# MineralFire_v1.net
KiCad netlist of a schematic drawn in EAGLE
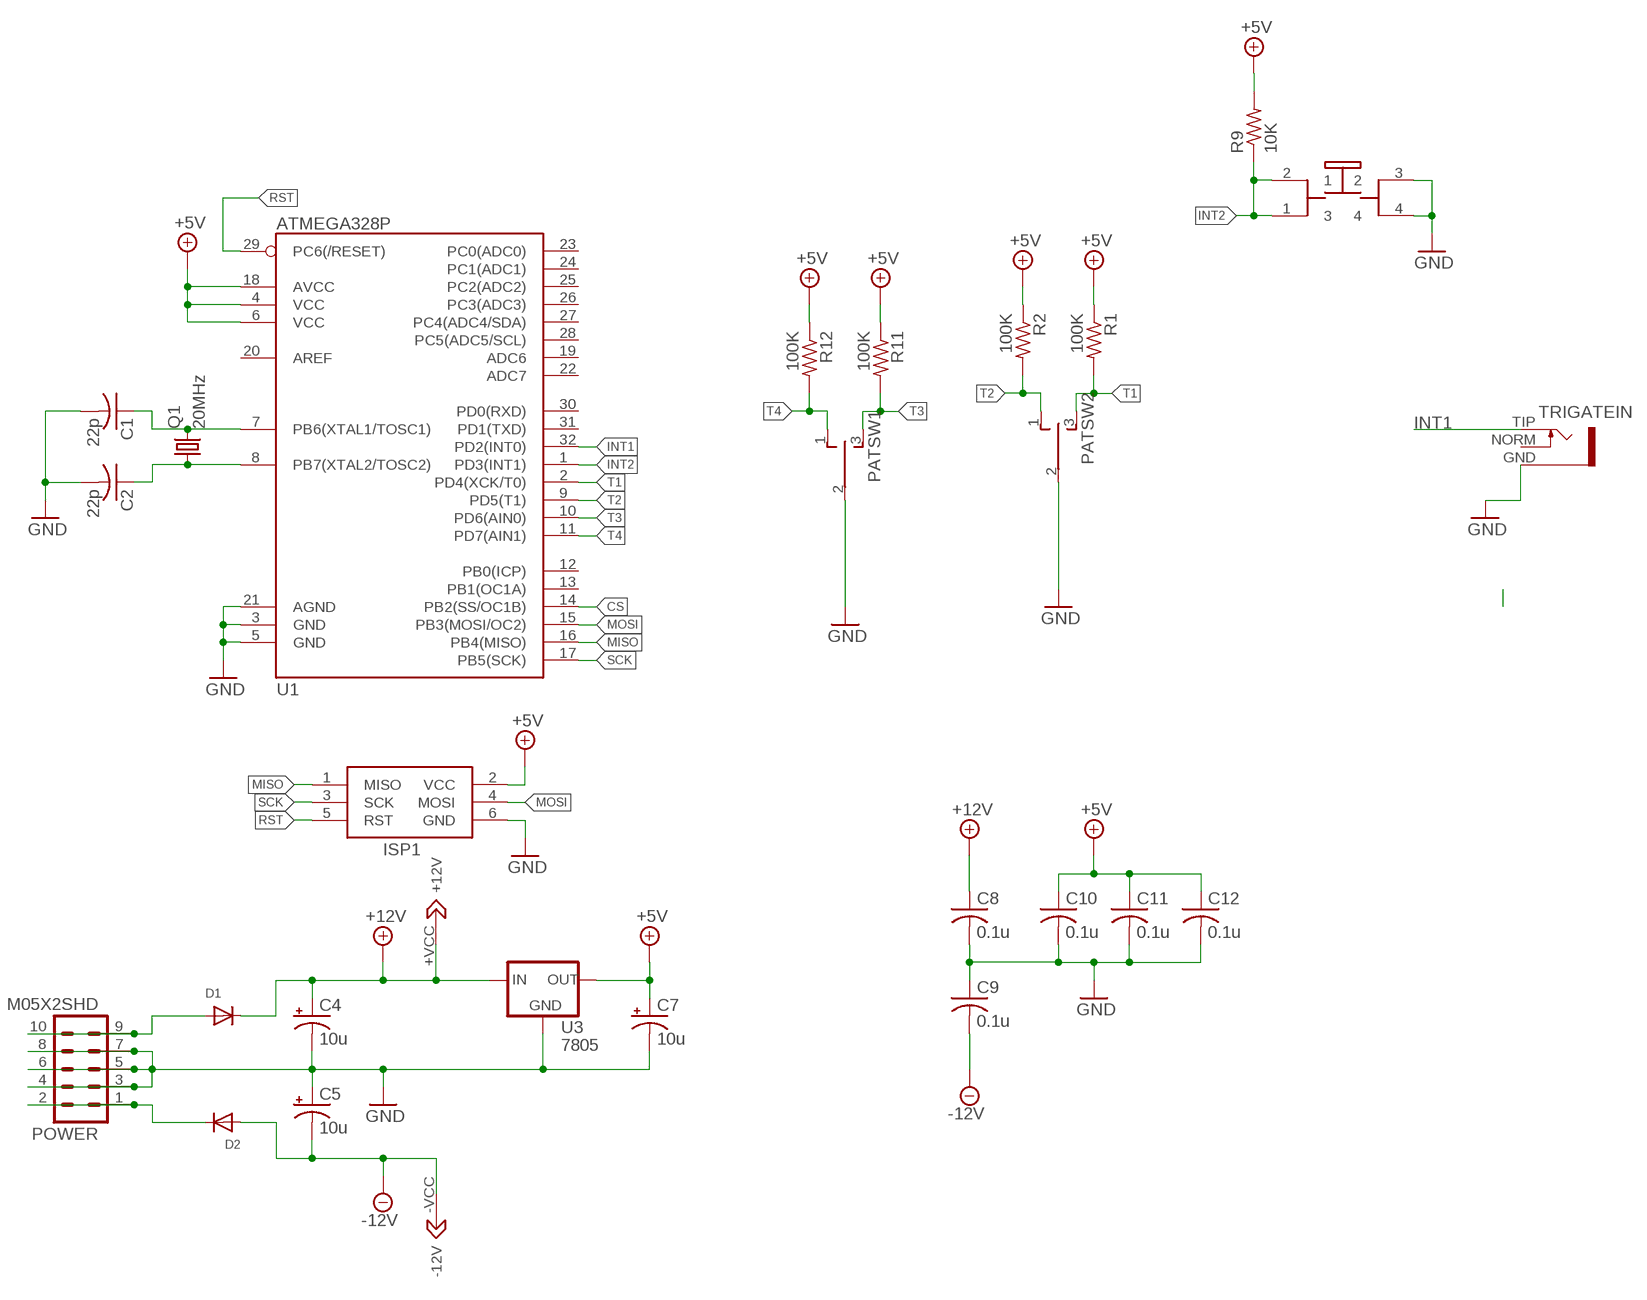
[diagram p0: schematic, sheet 1]

(export (version "E")
  (design (tool "Eeschema 10.0.6"))
  (components
    (comp (ref "BUT")
      (value "PB6149L-5")
      (footprint "eagle-import:PB6149L")
      (libsource (lib "eagle-import") (part "PB6149L-5"))
    )
    (comp (ref "C1")
      (value "22p")
      (footprint "eagle-import:C0805K")
      (libsource (lib "eagle-import") (part "C-USC0805K"))
    )
    (comp (ref "C2")
      (value "22p")
      (footprint "eagle-import:C0805K")
      (libsource (lib "eagle-import") (part "C-USC0805K"))
    )
    (comp (ref "C4")
      (value "10u")
      (footprint "eagle-import:153CLV-0505")
      (libsource (lib "eagle-import") (part "CPOL-US153CLV-0505"))
    )
    (comp (ref "C5")
      (value "10u")
      (footprint "eagle-import:153CLV-0505")
      (libsource (lib "eagle-import") (part "CPOL-US153CLV-0505"))
    )
    (comp (ref "C7")
      (value "10u")
      (footprint "eagle-import:153CLV-0505")
      (libsource (lib "eagle-import") (part "CPOL-US153CLV-0505"))
    )
    (comp (ref "C8")
      (value "0.1u")
      (footprint "eagle-import:C0805K")
      (libsource (lib "eagle-import") (part "C-USC0805K"))
    )
    (comp (ref "C9")
      (value "0.1u")
      (footprint "eagle-import:C0805K")
      (libsource (lib "eagle-import") (part "C-USC0805K"))
    )
    (comp (ref "C10")
      (value "0.1u")
      (footprint "eagle-import:C0805K")
      (libsource (lib "eagle-import") (part "C-USC0805K"))
    )
    (comp (ref "C11")
      (value "0.1u")
      (footprint "eagle-import:C0805K")
      (libsource (lib "eagle-import") (part "C-USC0805K"))
    )
    (comp (ref "C12")
      (value "0.1u")
      (footprint "eagle-import:C0805K")
      (libsource (lib "eagle-import") (part "C-USC0805K"))
    )
    (comp (ref "D1")
      (value "DIODESMA")
      (footprint "eagle-import:SMADIODE")
      (libsource (lib "eagle-import") (part "DIODESMA"))
    )
    (comp (ref "D2")
      (value "DIODESMA")
      (footprint "eagle-import:SMADIODE")
      (libsource (lib "eagle-import") (part "DIODESMA"))
    )
    (comp (ref "ISP1")
      (value "AVRISP-6")
      (footprint "eagle-import:AVRISP")
      (libsource (lib "eagle-import") (part "AVRISP-6"))
    )
    (comp (ref "PATSW1")
      (value "TOGGLE_ON_OFF_ON")
      (footprint "eagle-import:TOGGLE_ON_OFF_ON")
      (libsource (lib "eagle-import") (part "TOGGLE_ON_OFF_ON"))
    )
    (comp (ref "PATSW2")
      (value "TOGGLE_ON_OFF_ON")
      (footprint "eagle-import:TOGGLE_ON_OFF_ON")
      (libsource (lib "eagle-import") (part "TOGGLE_ON_OFF_ON"))
    )
    (comp (ref "POWER")
      (value "M05X2SHD")
      (footprint "eagle-import:2X5-SHROUDED")
      (libsource (lib "eagle-import") (part "M05X2SHD"))
    )
    (comp (ref "Q1")
      (value "20MHz")
      (footprint "eagle-import:HC49UP")
      (libsource (lib "eagle-import") (part "CRYSTALHC49UP"))
    )
    (comp (ref "R1")
      (value "100K")
      (footprint "eagle-import:R0805")
      (libsource (lib "eagle-import") (part "R-US_R0805"))
    )
    (comp (ref "R2")
      (value "100K")
      (footprint "eagle-import:R0805")
      (libsource (lib "eagle-import") (part "R-US_R0805"))
    )
    (comp (ref "R9")
      (value "10K")
      (footprint "eagle-import:R0805")
      (libsource (lib "eagle-import") (part "R-US_R0805"))
    )
    (comp (ref "R11")
      (value "100K")
      (footprint "eagle-import:R0805")
      (libsource (lib "eagle-import") (part "R-US_R0805"))
    )
    (comp (ref "R12")
      (value "100K")
      (footprint "eagle-import:R0805")
      (libsource (lib "eagle-import") (part "R-US_R0805"))
    )
    (comp (ref "TRIGATEIN")
      (value "S_JACK")
      (footprint "eagle-import:S_JACK")
      (libsource (lib "eagle-import") (part "S_JACK"))
    )
    (comp (ref "U1")
      (value "ATMEGA328P")
      (footprint "eagle-import:TQFP32-08")
      (libsource (lib "eagle-import") (part "ATMEGA328_SMT"))
    )
    (comp (ref "U2")
      (value "DUAL_OPAMP")
      (footprint "eagle-import:DUAL_OPAMP")
      (libsource (lib "eagle-import") (part "DUAL_OPAMP"))
    )
    (comp (ref "U3")
      (value "7805")
      (footprint "eagle-import:V-REG")
      (libsource (lib "eagle-import") (part "V-REG"))
    )
  )
  (nets
    (net (code "1") (name "+5V") (class "Default")
      (node (ref "C10") (pin "1") (pinfunction "1_1") (pintype "passive"))
      (node (ref "C11") (pin "1") (pinfunction "1_1") (pintype "passive"))
      (node (ref "C12") (pin "1") (pinfunction "1_1") (pintype "passive"))
      (node (ref "C7") (pin "+") (pinfunction "+_+") (pintype "passive"))
      (node (ref "ISP1") (pin "2") (pinfunction "VCC_2") (pintype "power_in"))
      (node (ref "R1") (pin "1") (pinfunction "1_1") (pintype "passive"))
      (node (ref "R11") (pin "1") (pinfunction "1_1") (pintype "passive"))
      (node (ref "R12") (pin "1") (pinfunction "1_1") (pintype "passive"))
      (node (ref "R2") (pin "1") (pinfunction "1_1") (pintype "passive"))
      (node (ref "R9") (pin "2") (pinfunction "2_2") (pintype "passive"))
      (node (ref "U1") (pin "18") (pinfunction "AVCC_18") (pintype "bidirectional"))
      (node (ref "U1") (pin "4") (pinfunction "VCC_4") (pintype "bidirectional"))
      (node (ref "U1") (pin "6") (pinfunction "VCC_6") (pintype "bidirectional"))
      (node (ref "U3") (pin "3") (pinfunction "OUT_3") (pintype "passive"))
    )
    (net (code "2") (name "+12V") (class "Default")
      (node (ref "C4") (pin "+") (pinfunction "+_+") (pintype "passive"))
      (node (ref "C8") (pin "1") (pinfunction "1_1") (pintype "passive"))
      (node (ref "D1") (pin "C") (pinfunction "C_C") (pintype "passive"))
      (node (ref "U2") (pin "+VCC") (pinfunction "+12V_+VCC") (pintype "bidirectional"))
      (node (ref "U3") (pin "1") (pinfunction "IN_1") (pintype "input"))
    )
    (net (code "3") (name "-12V") (class "Default")
      (node (ref "C5") (pin "-") (pinfunction "-_-") (pintype "passive"))
      (node (ref "C9") (pin "2") (pinfunction "2_2") (pintype "passive"))
      (node (ref "D2") (pin "A") (pinfunction "A_A") (pintype "passive"))
      (node (ref "U2") (pin "-VCC") (pinfunction "-12V_-VCC") (pintype "bidirectional"))
    )
    (net (code "4") (name "CS") (class "Default")
      (node (ref "U1") (pin "14") (pinfunction "PB2(SS/OC1B)_14") (pintype "bidirectional"))
    )
    (net (code "5") (name "GND") (class "Default")
      (node (ref "BUT") (pin "3") (pinfunction "2_3") (pintype "bidirectional"))
      (node (ref "BUT") (pin "4") (pinfunction "4_4") (pintype "bidirectional"))
      (node (ref "C1") (pin "2") (pinfunction "2_2") (pintype "passive"))
      (node (ref "C10") (pin "2") (pinfunction "2_2") (pintype "passive"))
      (node (ref "C11") (pin "2") (pinfunction "2_2") (pintype "passive"))
      (node (ref "C12") (pin "2") (pinfunction "2_2") (pintype "passive"))
      (node (ref "C2") (pin "2") (pinfunction "2_2") (pintype "passive"))
      (node (ref "C4") (pin "-") (pinfunction "-_-") (pintype "passive"))
      (node (ref "C5") (pin "+") (pinfunction "+_+") (pintype "passive"))
      (node (ref "C7") (pin "-") (pinfunction "-_-") (pintype "passive"))
      (node (ref "C8") (pin "2") (pinfunction "2_2") (pintype "passive"))
      (node (ref "C9") (pin "1") (pinfunction "1_1") (pintype "passive"))
      (node (ref "ISP1") (pin "6") (pinfunction "GND_6") (pintype "power_in"))
      (node (ref "PATSW1") (pin "2") (pinfunction "P_2") (pintype "passive"))
      (node (ref "PATSW2") (pin "2") (pinfunction "P_2") (pintype "passive"))
      (node (ref "POWER") (pin "3") (pinfunction "3_3") (pintype "passive"))
      (node (ref "POWER") (pin "4") (pinfunction "4_4") (pintype "passive"))
      (node (ref "POWER") (pin "5") (pinfunction "5_5") (pintype "passive"))
      (node (ref "POWER") (pin "6") (pinfunction "6_6") (pintype "passive"))
      (node (ref "POWER") (pin "7") (pinfunction "7_7") (pintype "passive"))
      (node (ref "POWER") (pin "8") (pinfunction "8_8") (pintype "passive"))
      (node (ref "TRIGATEIN") (pin "GND") (pinfunction "GND_GND") (pintype "passive"))
      (node (ref "U1") (pin "21") (pinfunction "AGND_21") (pintype "bidirectional"))
      (node (ref "U1") (pin "3") (pinfunction "GND_3") (pintype "bidirectional"))
      (node (ref "U1") (pin "5") (pinfunction "GND_5") (pintype "bidirectional"))
      (node (ref "U3") (pin "4") (pinfunction "GND_4") (pintype "input"))
    )
    (net (code "6") (name "INT1") (class "Default")
      (node (ref "TRIGATEIN") (pin "TIP") (pinfunction "TIP_TIP") (pintype "passive"))
      (node (ref "U1") (pin "32") (pinfunction "PD2(INT0)_32") (pintype "bidirectional"))
    )
    (net (code "7") (name "INT2") (class "Default")
      (node (ref "BUT") (pin "1") (pinfunction "3_1") (pintype "bidirectional"))
      (node (ref "BUT") (pin "2") (pinfunction "1_2") (pintype "bidirectional"))
      (node (ref "R9") (pin "1") (pinfunction "1_1") (pintype "passive"))
      (node (ref "U1") (pin "1") (pinfunction "PD3(INT1)_1") (pintype "bidirectional"))
    )
    (net (code "8") (name "MISO") (class "Default")
      (node (ref "ISP1") (pin "1") (pinfunction "MISO_1") (pintype "input"))
      (node (ref "U1") (pin "16") (pinfunction "PB4(MISO)_16") (pintype "bidirectional"))
    )
    (net (code "9") (name "MOSI") (class "Default")
      (node (ref "ISP1") (pin "4") (pinfunction "MOSI_4") (pintype "output"))
      (node (ref "U1") (pin "15") (pinfunction "PB3(MOSI/OC2)_15") (pintype "bidirectional"))
    )
    (net (code "10") (name "Net-(D1-PadA)") (class "Default")
      (node (ref "D1") (pin "A") (pinfunction "A_A") (pintype "passive"))
      (node (ref "POWER") (pin "10") (pinfunction "10_10") (pintype "passive"))
      (node (ref "POWER") (pin "9") (pinfunction "9_9") (pintype "passive"))
    )
    (net (code "11") (name "Net-(D2-PadC)") (class "Default")
      (node (ref "D2") (pin "C") (pinfunction "C_C") (pintype "passive"))
      (node (ref "POWER") (pin "1") (pinfunction "1_1") (pintype "passive"))
      (node (ref "POWER") (pin "2") (pinfunction "2_2") (pintype "passive"))
    )
    (net (code "12") (name "Net-(U1-PB6(XTAL1{slash}TOSC1))") (class "Default")
      (node (ref "C1") (pin "1") (pinfunction "1_1") (pintype "passive"))
      (node (ref "Q1") (pin "2") (pinfunction "2_2") (pintype "passive"))
      (node (ref "U1") (pin "7") (pinfunction "PB6(XTAL1/TOSC1)_7") (pintype "bidirectional"))
    )
    (net (code "13") (name "Net-(U1-PB7(XTAL2{slash}TOSC2))") (class "Default")
      (node (ref "C2") (pin "1") (pinfunction "1_1") (pintype "passive"))
      (node (ref "Q1") (pin "1") (pinfunction "1_1") (pintype "passive"))
      (node (ref "U1") (pin "8") (pinfunction "PB7(XTAL2/TOSC2)_8") (pintype "bidirectional"))
    )
    (net (code "14") (name "RST") (class "Default")
      (node (ref "ISP1") (pin "5") (pinfunction "RST_5") (pintype "output"))
      (node (ref "U1") (pin "29") (pinfunction "PC6(/RESET)_29") (pintype "bidirectional"))
    )
    (net (code "15") (name "SCK") (class "Default")
      (node (ref "ISP1") (pin "3") (pinfunction "SCK_3") (pintype "output"))
      (node (ref "U1") (pin "17") (pinfunction "PB5(SCK)_17") (pintype "bidirectional"))
    )
    (net (code "16") (name "T1") (class "Default")
      (node (ref "PATSW2") (pin "3") (pinfunction "S_3") (pintype "passive"))
      (node (ref "R1") (pin "2") (pinfunction "2_2") (pintype "passive"))
      (node (ref "U1") (pin "2") (pinfunction "PD4(XCK/T0)_2") (pintype "bidirectional"))
    )
    (net (code "17") (name "T2") (class "Default")
      (node (ref "PATSW2") (pin "1") (pinfunction "O_1") (pintype "passive"))
      (node (ref "R2") (pin "2") (pinfunction "2_2") (pintype "passive"))
      (node (ref "U1") (pin "9") (pinfunction "PD5(T1)_9") (pintype "bidirectional"))
    )
    (net (code "18") (name "T3") (class "Default")
      (node (ref "PATSW1") (pin "3") (pinfunction "S_3") (pintype "passive"))
      (node (ref "R11") (pin "2") (pinfunction "2_2") (pintype "passive"))
      (node (ref "U1") (pin "10") (pinfunction "PD6(AIN0)_10") (pintype "bidirectional"))
    )
    (net (code "19") (name "T4") (class "Default")
      (node (ref "PATSW1") (pin "1") (pinfunction "O_1") (pintype "passive"))
      (node (ref "R12") (pin "2") (pinfunction "2_2") (pintype "passive"))
      (node (ref "U1") (pin "11") (pinfunction "PD7(AIN1)_11") (pintype "bidirectional"))
    )
    (net (code "20") (name "unconnected-(TRIGATEIN-PadNORM)") (class "Default")
      (node (ref "TRIGATEIN") (pin "NORM") (pinfunction "NORM_NORM") (pintype "passive"))
    )
    (net (code "21") (name "unconnected-(U1-ADC6-Pad19)") (class "Default")
      (node (ref "U1") (pin "19") (pinfunction "ADC6_19") (pintype "bidirectional"))
    )
    (net (code "22") (name "unconnected-(U1-ADC7-Pad22)") (class "Default")
      (node (ref "U1") (pin "22") (pinfunction "ADC7_22") (pintype "bidirectional"))
    )
    (net (code "23") (name "unconnected-(U1-AREF-Pad20)") (class "Default")
      (node (ref "U1") (pin "20") (pinfunction "AREF_20") (pintype "bidirectional"))
    )
    (net (code "24") (name "unconnected-(U1-PB0(ICP)-Pad12)") (class "Default")
      (node (ref "U1") (pin "12") (pinfunction "PB0(ICP)_12") (pintype "bidirectional"))
    )
    (net (code "25") (name "unconnected-(U1-PB1(OC1A)-Pad13)") (class "Default")
      (node (ref "U1") (pin "13") (pinfunction "PB1(OC1A)_13") (pintype "bidirectional"))
    )
    (net (code "26") (name "unconnected-(U1-PC0(ADC0)-Pad23)") (class "Default")
      (node (ref "U1") (pin "23") (pinfunction "PC0(ADC0)_23") (pintype "bidirectional"))
    )
    (net (code "27") (name "unconnected-(U1-PC1(ADC1)-Pad24)") (class "Default")
      (node (ref "U1") (pin "24") (pinfunction "PC1(ADC1)_24") (pintype "bidirectional"))
    )
    (net (code "28") (name "unconnected-(U1-PC2(ADC2)-Pad25)") (class "Default")
      (node (ref "U1") (pin "25") (pinfunction "PC2(ADC2)_25") (pintype "bidirectional"))
    )
    (net (code "29") (name "unconnected-(U1-PC3(ADC3)-Pad26)") (class "Default")
      (node (ref "U1") (pin "26") (pinfunction "PC3(ADC3)_26") (pintype "bidirectional"))
    )
    (net (code "30") (name "unconnected-(U1-PC4(ADC4{slash}SDA)-Pad27)") (class "Default")
      (node (ref "U1") (pin "27") (pinfunction "PC4(ADC4/SDA)_27") (pintype "bidirectional"))
    )
    (net (code "31") (name "unconnected-(U1-PC5(ADC5{slash}SCL)-Pad28)") (class "Default")
      (node (ref "U1") (pin "28") (pinfunction "PC5(ADC5/SCL)_28") (pintype "bidirectional"))
    )
    (net (code "32") (name "unconnected-(U1-PD0(RXD)-Pad30)") (class "Default")
      (node (ref "U1") (pin "30") (pinfunction "PD0(RXD)_30") (pintype "bidirectional"))
    )
    (net (code "33") (name "unconnected-(U1-PD1(TXD)-Pad31)") (class "Default")
      (node (ref "U1") (pin "31") (pinfunction "PD1(TXD)_31") (pintype "bidirectional"))
    )
  )
)
